# tutuShield.net
KiCad netlist of a schematic drawn in EAGLE
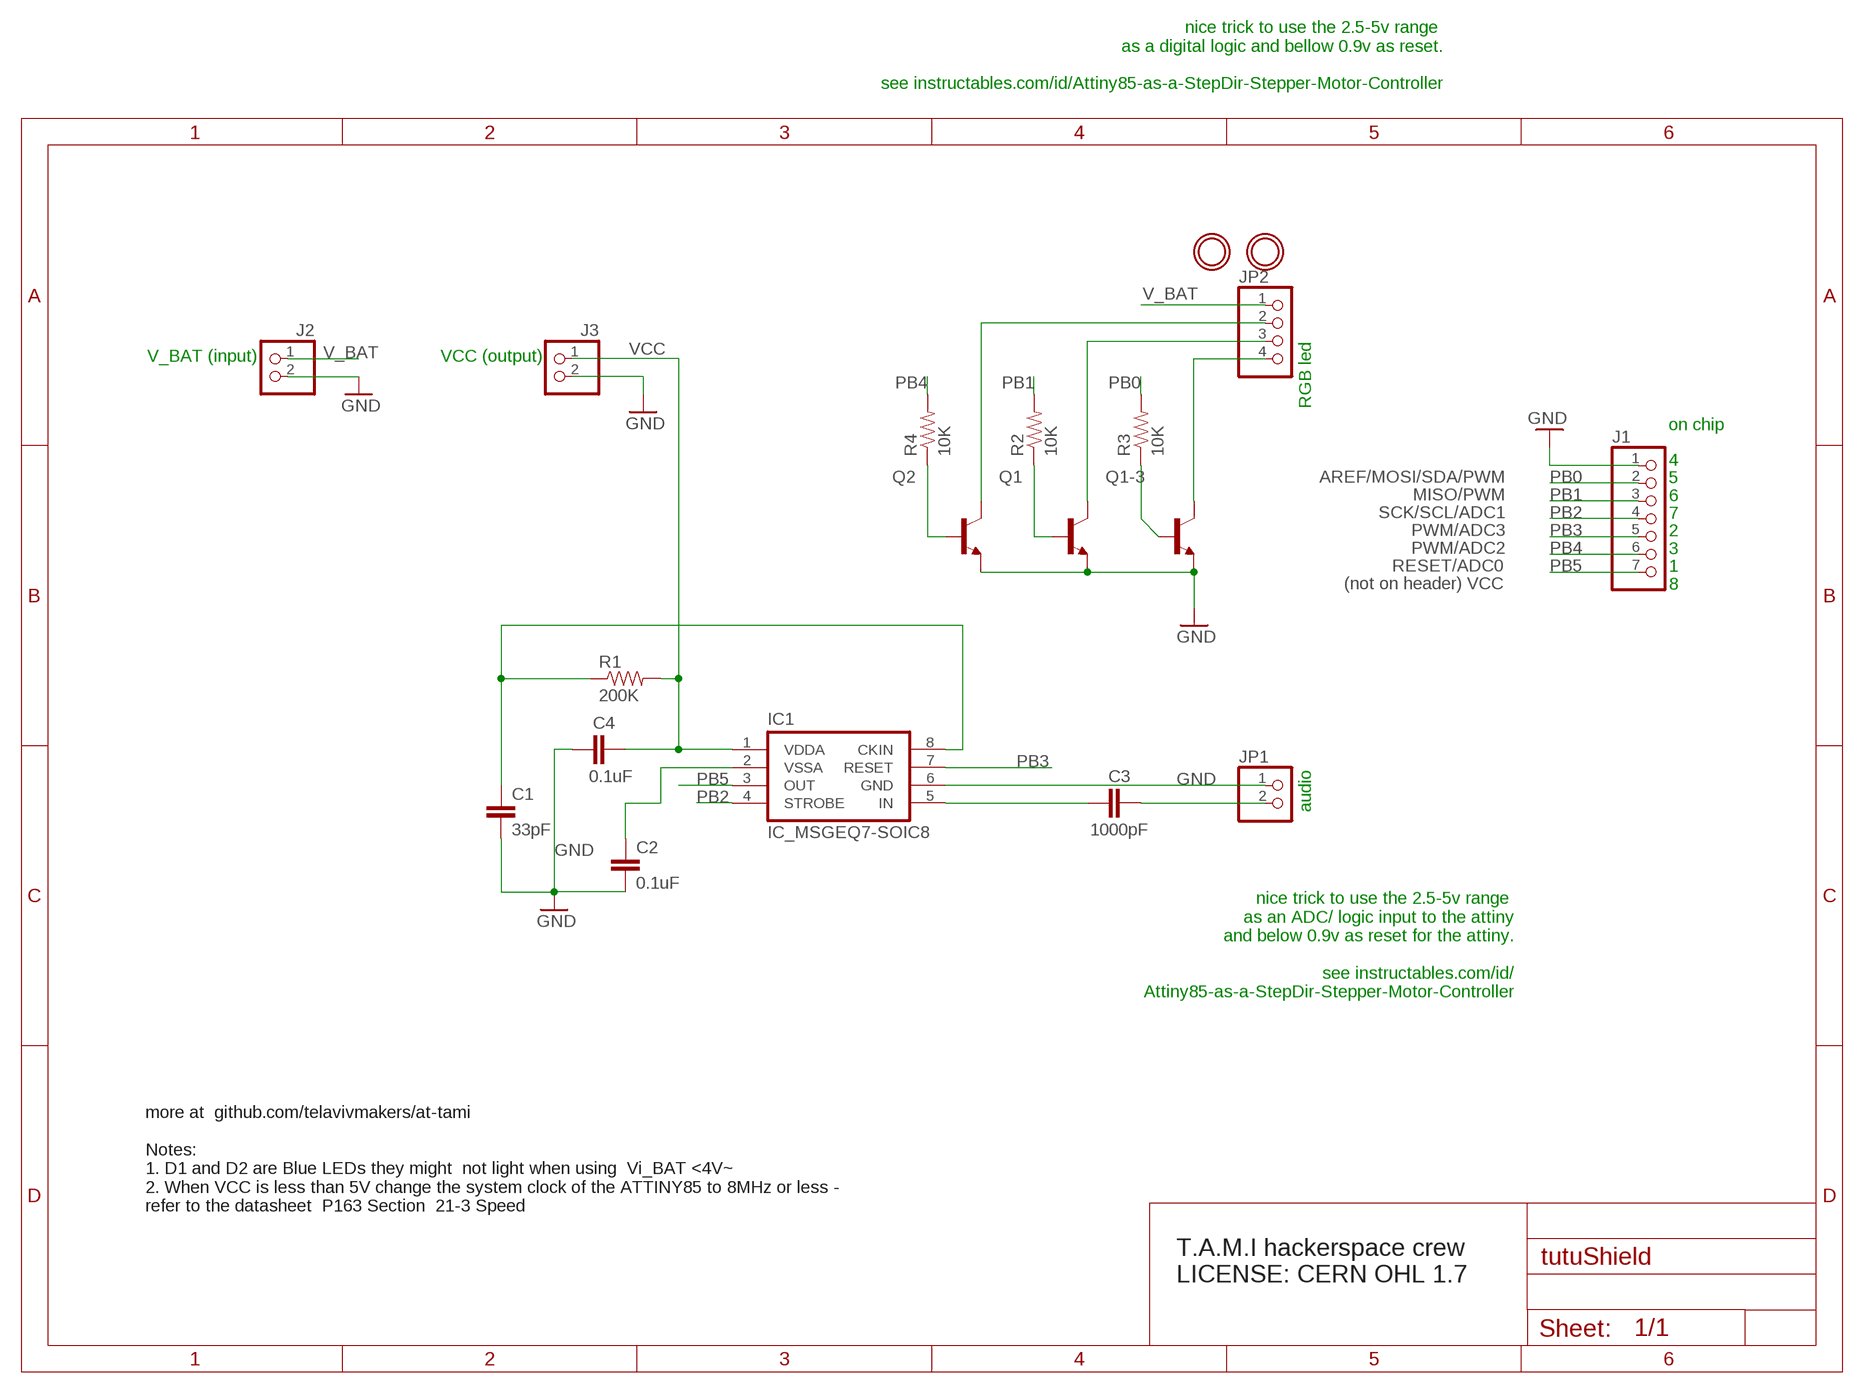
[diagram p0: schematic, sheet 1]

(export (version "E")
  (design (tool "Eeschema 10.0.6"))
  (components
    (comp (ref "C1")
      (value "33pF")
      (footprint "eagle-import:0805")
      (libsource (lib "eagle-import") (part "CAP0805"))
    )
    (comp (ref "C2")
      (value "0.1uF")
      (footprint "eagle-import:0805")
      (libsource (lib "eagle-import") (part "CAP0805"))
    )
    (comp (ref "C3")
      (value "1000pF")
      (footprint "eagle-import:0805")
      (libsource (lib "eagle-import") (part "CAP0805"))
    )
    (comp (ref "C4")
      (value "0.1uF")
      (footprint "eagle-import:0805")
      (libsource (lib "eagle-import") (part "CAP0805"))
    )
    (comp (ref "IC1")
      (value "IC_MSGEQ7-SOIC8")
      (footprint "eagle-import:SOIC-8")
      (libsource (lib "eagle-import") (part "IC_MSGEQ7-SOIC8"))
    )
    (comp (ref "J1")
      (value "HEADER-1X7ROUND")
      (footprint "eagle-import:1X07_ROUND")
      (libsource (lib "eagle-import") (part "HEADER-1X7ROUND"))
    )
    (comp (ref "J2")
      (value "HEADER-1X2ROUND")
      (footprint "eagle-import:1X02_ROUND")
      (libsource (lib "eagle-import") (part "microbuilder_HEADER-1X2ROUND"))
    )
    (comp (ref "J3")
      (value "HEADER-1X2ROUND")
      (footprint "eagle-import:1X02_ROUND")
      (libsource (lib "eagle-import") (part "microbuilder_HEADER-1X2ROUND"))
    )
    (comp (ref "JP1")
      (value "HEADER-1X2ROUND")
      (footprint "eagle-import:1X02_ROUND")
      (libsource (lib "eagle-import") (part "HEADER-1X2ROUND"))
    )
    (comp (ref "JP2")
      (value "HEADER-1X4ROUND")
      (footprint "eagle-import:1X04_ROUND")
      (libsource (lib "eagle-import") (part "HEADER-1X4ROUND"))
    )
    (comp (ref "Q1")
      (value "TRANSISTOR_BJT_NPN-SOT-23-BEC")
      (footprint "eagle-import:SOT-23")
      (libsource (lib "eagle-import") (part "TRANSISTOR_BJT_NPN-SOT-23-BEC"))
    )
    (comp (ref "Q1-3")
      (value "TRANSISTOR_BJT_NPN-SOT-23-BEC")
      (footprint "eagle-import:SOT-23")
      (libsource (lib "eagle-import") (part "TRANSISTOR_BJT_NPN-SOT-23-BEC"))
    )
    (comp (ref "Q2")
      (value "TRANSISTOR_BJT_NPN-SOT-23-BEC")
      (footprint "eagle-import:SOT-23")
      (libsource (lib "eagle-import") (part "TRANSISTOR_BJT_NPN-SOT-23-BEC"))
    )
    (comp (ref "R1")
      (value "200K")
      (footprint "eagle-import:0805")
      (libsource (lib "eagle-import") (part "RESISTOR0805-RES"))
    )
    (comp (ref "R2")
      (value "10K")
      (footprint "eagle-import:0805")
      (libsource (lib "eagle-import") (part "RESISTOR0805-RES"))
    )
    (comp (ref "R3")
      (value "10K")
      (footprint "eagle-import:0805")
      (libsource (lib "eagle-import") (part "RESISTOR0805-RES"))
    )
    (comp (ref "R4")
      (value "10K")
      (footprint "eagle-import:0805")
      (libsource (lib "eagle-import") (part "RESISTOR0805-RES"))
    )
    (comp (ref "U$1")
      (value "MOUNTINGHOLE2.0")
      (footprint "eagle-import:MOUNTINGHOLE_2.0_PLATED")
      (libsource (lib "eagle-import") (part "MOUNTINGHOLE2.0"))
    )
    (comp (ref "U$2")
      (value "MOUNTINGHOLE2.0")
      (footprint "eagle-import:MOUNTINGHOLE_2.0_PLATED")
      (libsource (lib "eagle-import") (part "MOUNTINGHOLE2.0"))
    )
  )
  (nets
    (net (code "1") (name "/PB0") (class "Default")
      (node (ref "J1") (pin "2") (pinfunction "2_2") (pintype "passive"))
      (node (ref "R3") (pin "2") (pinfunction "2_2") (pintype "passive"))
    )
    (net (code "2") (name "/PB1") (class "Default")
      (node (ref "J1") (pin "3") (pinfunction "3_3") (pintype "passive"))
      (node (ref "R2") (pin "2") (pinfunction "2_2") (pintype "passive"))
    )
    (net (code "3") (name "/PB2") (class "Default")
      (node (ref "IC1") (pin "4") (pinfunction "STROBE_4") (pintype "input"))
      (node (ref "J1") (pin "4") (pinfunction "4_4") (pintype "passive"))
    )
    (net (code "4") (name "/PB3") (class "Default")
      (node (ref "IC1") (pin "7") (pinfunction "RESET_7") (pintype "input"))
      (node (ref "J1") (pin "5") (pinfunction "5_5") (pintype "passive"))
    )
    (net (code "5") (name "/PB4") (class "Default")
      (node (ref "J1") (pin "6") (pinfunction "6_6") (pintype "passive"))
      (node (ref "R4") (pin "2") (pinfunction "2_2") (pintype "passive"))
    )
    (net (code "6") (name "/PB5") (class "Default")
      (node (ref "IC1") (pin "3") (pinfunction "OUT_3") (pintype "output"))
      (node (ref "J1") (pin "7") (pinfunction "7_7") (pintype "passive"))
    )
    (net (code "7") (name "/VCC") (class "Default")
      (node (ref "C4") (pin "2") (pinfunction "2_2") (pintype "passive"))
      (node (ref "IC1") (pin "1") (pinfunction "VDDA_1") (pintype "power_in"))
      (node (ref "J3") (pin "1") (pinfunction "1_1") (pintype "passive"))
      (node (ref "R1") (pin "2") (pinfunction "2_2") (pintype "passive"))
    )
    (net (code "8") (name "/V_BAT") (class "Default")
      (node (ref "J2") (pin "1") (pinfunction "1_1") (pintype "passive"))
      (node (ref "JP2") (pin "1") (pinfunction "1_1") (pintype "passive"))
    )
    (net (code "9") (name "GND") (class "Default")
      (node (ref "C1") (pin "2") (pinfunction "2_2") (pintype "passive"))
      (node (ref "C2") (pin "2") (pinfunction "2_2") (pintype "passive"))
      (node (ref "C4") (pin "1") (pinfunction "1_1") (pintype "passive"))
      (node (ref "IC1") (pin "6") (pinfunction "GND_6") (pintype "input"))
      (node (ref "J1") (pin "1") (pinfunction "1_1") (pintype "passive"))
      (node (ref "J2") (pin "2") (pinfunction "2_2") (pintype "passive"))
      (node (ref "J3") (pin "2") (pinfunction "2_2") (pintype "passive"))
      (node (ref "JP1") (pin "1") (pinfunction "1_1") (pintype "passive"))
      (node (ref "Q1") (pin "2") (pinfunction "E_2") (pintype "passive"))
      (node (ref "Q1-3") (pin "2") (pinfunction "E_2") (pintype "passive"))
      (node (ref "Q2") (pin "2") (pinfunction "E_2") (pintype "passive"))
    )
    (net (code "10") (name "Net-(C3-Pad2)") (class "Default")
      (node (ref "C3") (pin "2") (pinfunction "2_2") (pintype "passive"))
      (node (ref "JP1") (pin "2") (pinfunction "2_2") (pintype "passive"))
    )
    (net (code "11") (name "Net-(IC1-CKIN)") (class "Default")
      (node (ref "C1") (pin "1") (pinfunction "1_1") (pintype "passive"))
      (node (ref "IC1") (pin "8") (pinfunction "CKIN_8") (pintype "power_in"))
      (node (ref "R1") (pin "1") (pinfunction "1_1") (pintype "passive"))
    )
    (net (code "12") (name "Net-(IC1-IN)") (class "Default")
      (node (ref "C3") (pin "1") (pinfunction "1_1") (pintype "passive"))
      (node (ref "IC1") (pin "5") (pinfunction "IN_5") (pintype "power_in"))
    )
    (net (code "13") (name "Net-(IC1-VSSA)") (class "Default")
      (node (ref "C2") (pin "1") (pinfunction "1_1") (pintype "passive"))
      (node (ref "IC1") (pin "2") (pinfunction "VSSA_2") (pintype "input"))
    )
    (net (code "14") (name "Net-(Q1-3-B)") (class "Default")
      (node (ref "Q1-3") (pin "1") (pinfunction "B_1") (pintype "passive"))
      (node (ref "R3") (pin "1") (pinfunction "1_1") (pintype "passive"))
    )
    (net (code "15") (name "Net-(Q1-3-C)") (class "Default")
      (node (ref "JP2") (pin "4") (pinfunction "4_4") (pintype "passive"))
      (node (ref "Q1-3") (pin "3") (pinfunction "C_3") (pintype "passive"))
    )
    (net (code "16") (name "Net-(Q1-B)") (class "Default")
      (node (ref "Q1") (pin "1") (pinfunction "B_1") (pintype "passive"))
      (node (ref "R2") (pin "1") (pinfunction "1_1") (pintype "passive"))
    )
    (net (code "17") (name "Net-(Q1-C)") (class "Default")
      (node (ref "JP2") (pin "3") (pinfunction "3_3") (pintype "passive"))
      (node (ref "Q1") (pin "3") (pinfunction "C_3") (pintype "passive"))
    )
    (net (code "18") (name "Net-(Q2-B)") (class "Default")
      (node (ref "Q2") (pin "1") (pinfunction "B_1") (pintype "passive"))
      (node (ref "R4") (pin "1") (pinfunction "1_1") (pintype "passive"))
    )
    (net (code "19") (name "Net-(Q2-C)") (class "Default")
      (node (ref "JP2") (pin "2") (pinfunction "2_2") (pintype "passive"))
      (node (ref "Q2") (pin "3") (pinfunction "C_3") (pintype "passive"))
    )
  )
)
